# microcontroller.net
KiCad netlist of a schematic drawn in Altium Designer
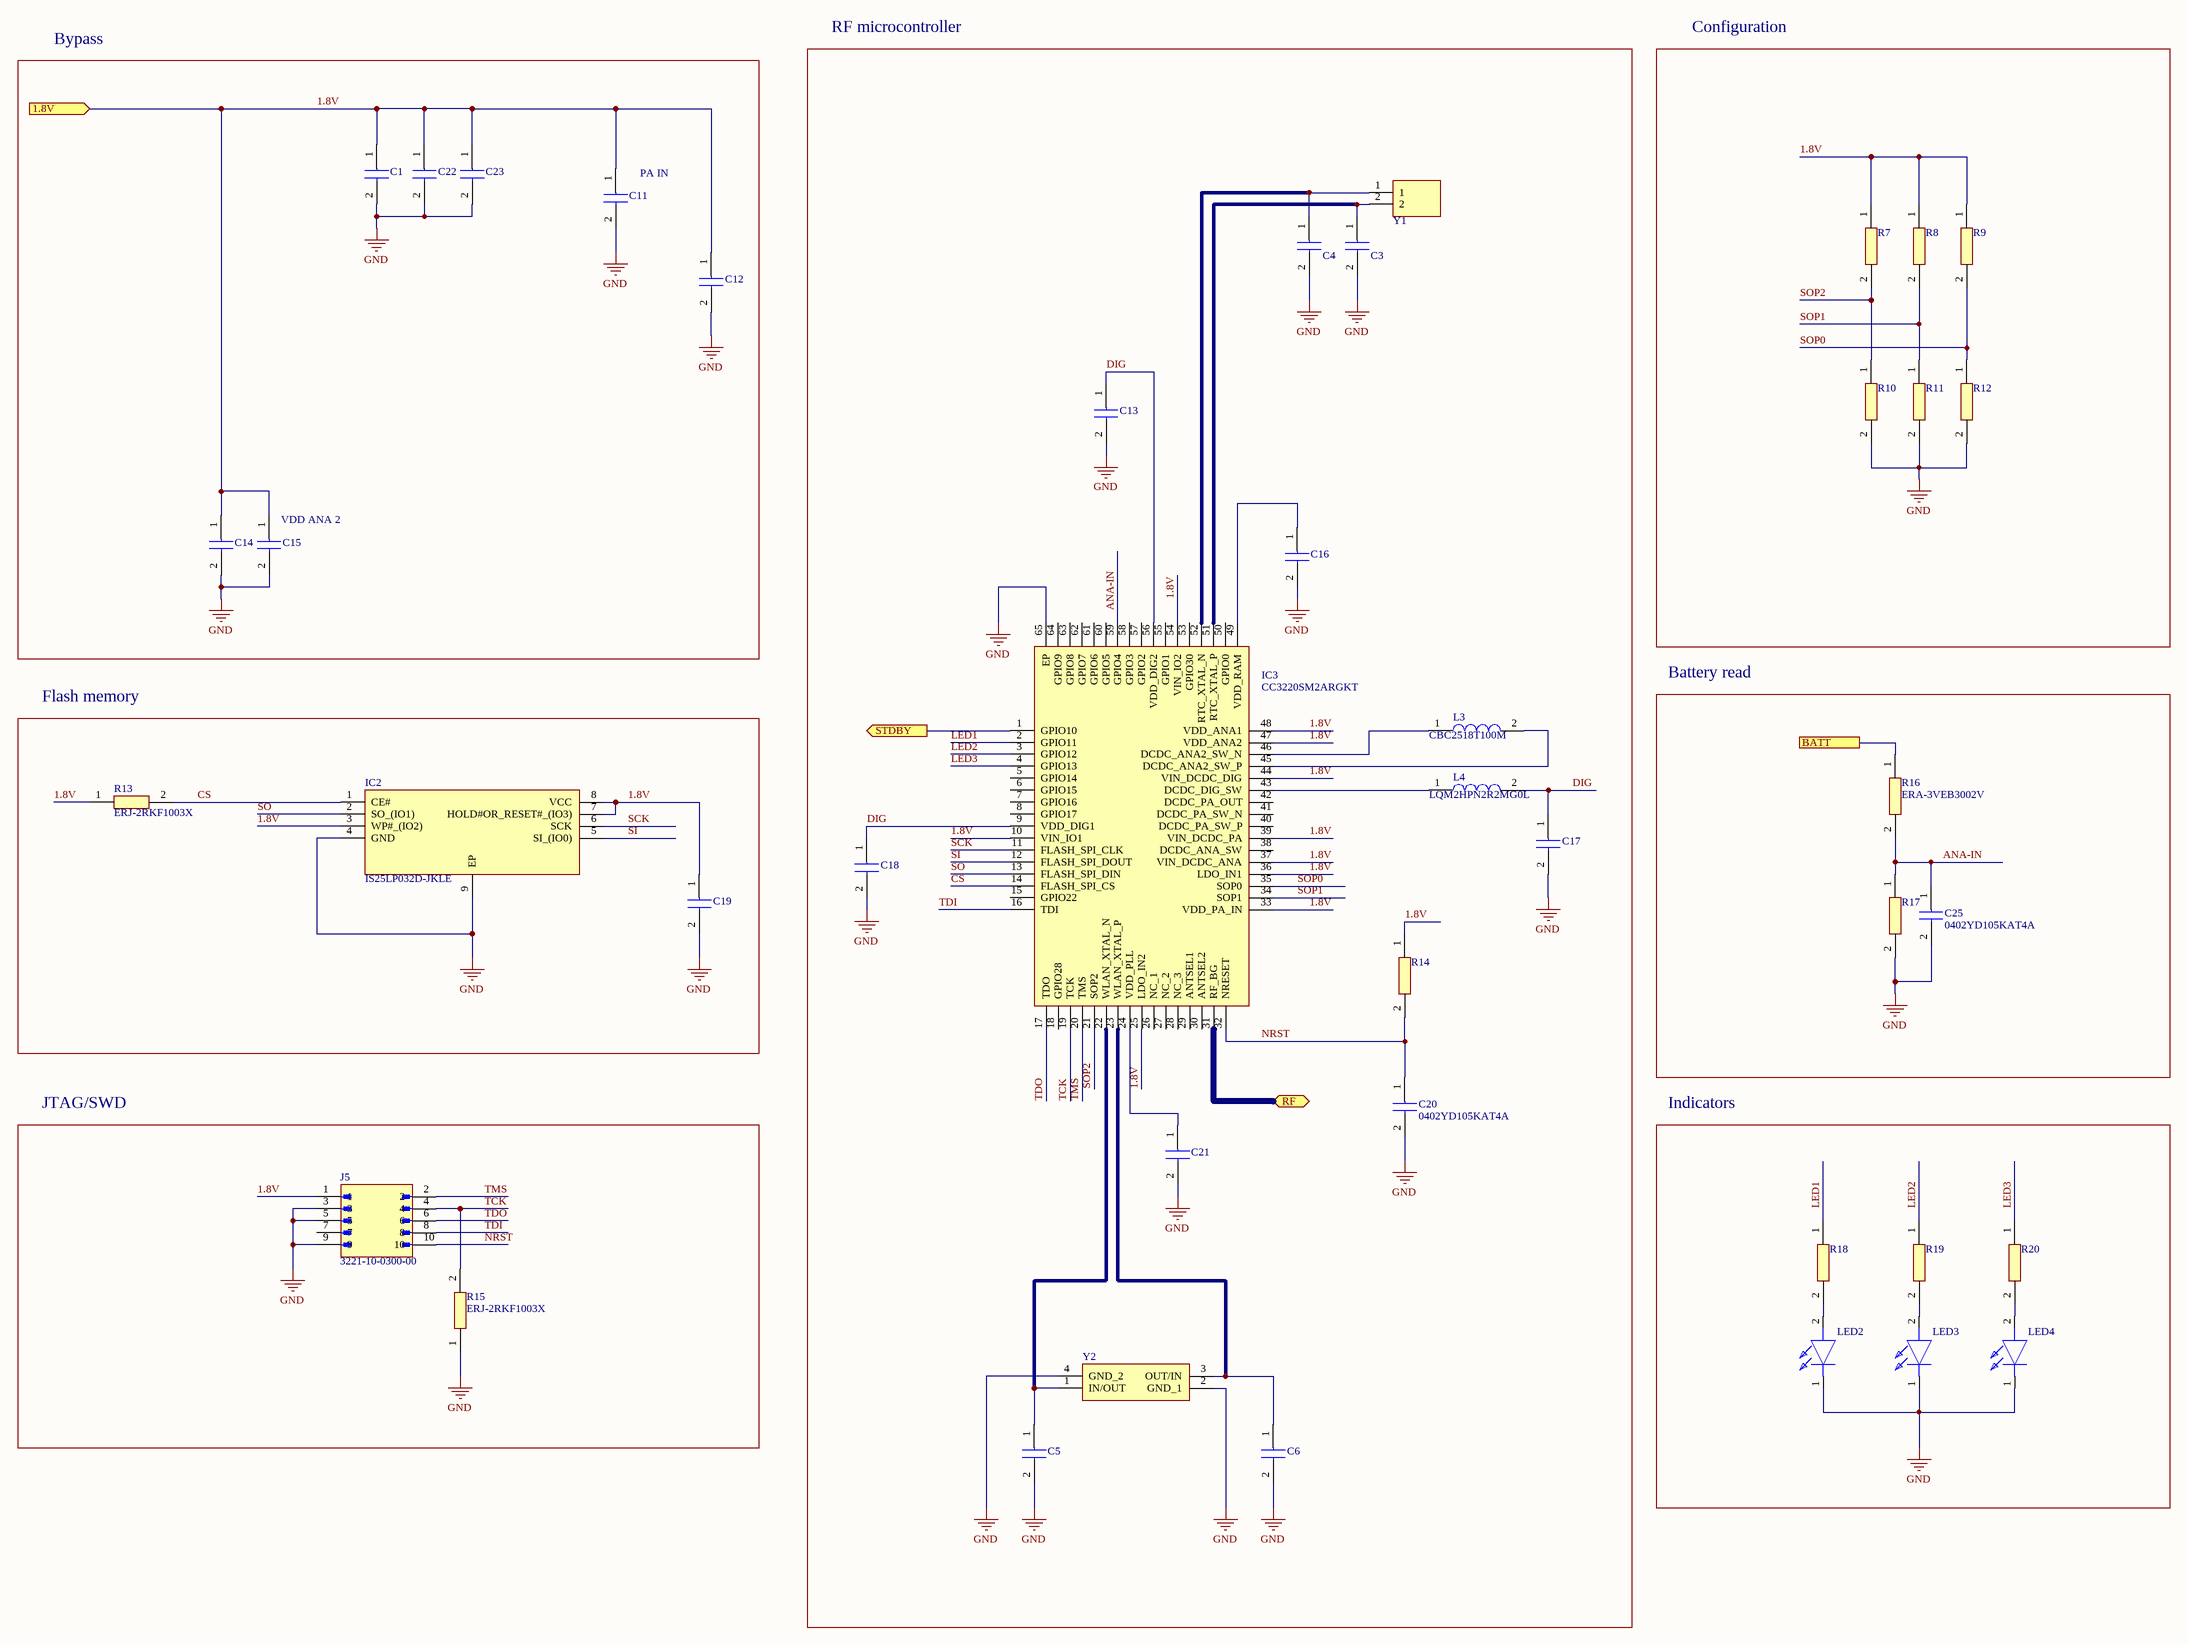
[diagram p0: microcontroller.SchDoc]

(export (version "E")
  (design (tool "Eeschema 10.0.6"))
  (components
    (comp (ref "C1")
      (value "C1005X5R0J475M050BC")
      (footprint "SamacSys:C1005_Commercial")
      (description "Capacitor")
      (fields (field (name "MOUSER PART NUMBER") "810-C1005X5R0J475M"))
      (libsource (lib "*") (part "C1005X5R0J475M050BC"))
    )
    (comp (ref "C3")
      (value "GRM1555C1H100JA01D")
      (footprint "SamacSys:CAPC1005X55N")
      (description "Capacitor")
      (fields (field (name "MOUSER PART NUMBER") "81-GRM1555C1H100JA1D"))
      (libsource (lib "*") (part "GRM1555C1H100JA01D"))
    )
    (comp (ref "C4")
      (value "GRM1555C1H100JA01D")
      (footprint "SamacSys:CAPC1005X55N")
      (description "Capacitor")
      (fields (field (name "MOUSER PART NUMBER") "81-GRM1555C1H100JA1D"))
      (libsource (lib "*") (part "GRM1555C1H100JA01D"))
    )
    (comp (ref "C5")
      (value "GRM1555C1H6R2CA01D")
      (footprint "SamacSys:CAPC1005X55N")
      (description "Capacitor")
      (fields (field (name "MOUSER PART NUMBER") "81-GRM1555C1H6R2CA1D"))
      (libsource (lib "*") (part "GRM1555C1H6R2CA01D"))
    )
    (comp (ref "C6")
      (value "GRM1555C1H6R2CA01D")
      (footprint "SamacSys:CAPC1005X55N")
      (description "Capacitor")
      (fields (field (name "MOUSER PART NUMBER") "81-GRM1555C1H6R2CA1D"))
      (libsource (lib "*") (part "GRM1555C1H6R2CA01D"))
    )
    (comp (ref "C11")
      (value "GRM158R60J226ME01D")
      (footprint "SamacSys:CAPC1005X80N")
      (description "Capacitor")
      (fields (field (name "MOUSER PART NUMBER") "81-GRM158R60J226ME1D"))
      (libsource (lib "*") (part "GRM158R60J226ME01D"))
    )
    (comp (ref "C12")
      (value "0402YD105KAT4A")
      (footprint "SamacSys:CAPC1005X56N")
      (description "Capacitor")
      (fields (field (name "MOUSER PART NUMBER") "581-0402YD105KAT4A"))
      (libsource (lib "*") (part "0402YD105KAT4A"))
    )
    (comp (ref "C13")
      (value "C1005X7R1C104K050BC")
      (footprint "SamacSys:C1005_Commercial")
      (description "Capacitor")
      (fields (field (name "MOUSER PART NUMBER") "810-C1005X7R1C104K"))
      (libsource (lib "*") (part "C1005X7R1C104K050BC"))
    )
    (comp (ref "C14")
      (value "GRM155C80G106ME44D")
      (footprint "SamacSys:CAPC1005X55N")
      (description "Capacitor")
      (fields (field (name "MOUSER PART NUMBER") "81-GRM155C80G106ME44"))
      (libsource (lib "*") (part "GRM155C80G106ME44D"))
    )
    (comp (ref "C15")
      (value "GRM155C80G106ME44D")
      (footprint "SamacSys:CAPC1005X55N")
      (description "Capacitor")
      (fields (field (name "MOUSER PART NUMBER") "81-GRM155C80G106ME44"))
      (libsource (lib "*") (part "GRM155C80G106ME44D"))
    )
    (comp (ref "C16")
      (value "C1005X7R1C104K050BC")
      (footprint "SamacSys:C1005_Commercial")
      (description "Capacitor")
      (fields (field (name "MOUSER PART NUMBER") "810-C1005X7R1C104K"))
      (libsource (lib "*") (part "C1005X7R1C104K050BC"))
    )
    (comp (ref "C17")
      (value "GRM155C80G106ME44D")
      (footprint "SamacSys:CAPC1005X55N")
      (description "Capacitor")
      (fields (field (name "MOUSER PART NUMBER") "81-GRM155C80G106ME44"))
      (libsource (lib "*") (part "GRM155C80G106ME44D"))
    )
    (comp (ref "C18")
      (value "C1005X7R1C104K050BC")
      (footprint "SamacSys:C1005_Commercial")
      (description "Capacitor")
      (fields (field (name "MOUSER PART NUMBER") "810-C1005X7R1C104K"))
      (libsource (lib "*") (part "C1005X7R1C104K050BC"))
    )
    (comp (ref "C19")
      (value "C1005X7R1C104K050BC")
      (footprint "SamacSys:C1005_Commercial")
      (description "Capacitor")
      (fields (field (name "MOUSER PART NUMBER") "810-C1005X7R1C104K"))
      (libsource (lib "*") (part "C1005X7R1C104K050BC"))
    )
    (comp (ref "C20")
      (value "0402YD105KAT4A")
      (footprint "SamacSys:CAPC1005X56N")
      (description "Capacitor")
      (fields (field (name "MOUSER PART NUMBER") "581-0402YD105KAT4A"))
      (libsource (lib "*") (part "0402YD105KAT4A"))
    )
    (comp (ref "C21")
      (value "C1005X7R1C104K050BC")
      (footprint "SamacSys:C1005_Commercial")
      (description "Capacitor")
      (fields (field (name "MOUSER PART NUMBER") "810-C1005X7R1C104K"))
      (libsource (lib "*") (part "C1005X7R1C104K050BC"))
    )
    (comp (ref "C22")
      (value "C1005X5R0J475M050BC")
      (footprint "SamacSys:C1005_Commercial")
      (description "Capacitor")
      (fields (field (name "MOUSER PART NUMBER") "810-C1005X5R0J475M"))
      (libsource (lib "*") (part "C1005X5R0J475M050BC"))
    )
    (comp (ref "C23")
      (value "C1005X5R0J475M050BC")
      (footprint "SamacSys:C1005_Commercial")
      (description "Capacitor")
      (fields (field (name "MOUSER PART NUMBER") "810-C1005X5R0J475M"))
      (libsource (lib "*") (part "C1005X5R0J475M050BC"))
    )
    (comp (ref "C25")
      (value "0402YD105KAT4A")
      (footprint "SamacSys:CAPC1005X56N")
      (description "Capacitor")
      (fields (field (name "MOUSER PART NUMBER") "581-0402YD105KAT4A"))
      (libsource (lib "*") (part "0402YD105KAT4A"))
    )
    (comp (ref "IC2")
      (value "IS25LP032D-JKLE")
      (footprint "SamacSys:SON127P600X500X80-9N-D")
      (description "Integrated Circuit")
      (fields (field (name "MOUSER PART NUMBER") "870-IS25LP032D-JKLE"))
      (libsource (lib "*") (part "IS25LP032D-JKLE"))
    )
    (comp (ref "IC3")
      (value "CC3220SM2ARGKT")
      (footprint "SamacSys:QFN50P900X900X100-65N-D")
      (description "Integrated Circuit")
      (fields (field (name "MOUSER PART NUMBER") "595-CC3220SM2ARGKT"))
      (libsource (lib "*") (part "CC3220SM2ARGKT"))
    )
    (comp (ref "J5")
      (value "3221-10-0300-00")
      (footprint "CNC_3221-10-0300-00")
      (description "Connector Header Surface Mount 10 position 0.050 (1.27mm)")
      (fields (field (name "MF") "CNC Tech"))
      (libsource (lib "3221-10-0300-00") (part "3221-10-0300-00"))
    )
    (comp (ref "L3")
      (value "CBC2518T100M")
      (footprint "SamacSys:INDC2518X180N")
      (description "Inductor")
      (fields (field (name "MOUSER PART NUMBER") "963-CBC2518T100M"))
      (libsource (lib "SamacSys") (part "CBC2518T100M"))
    )
    (comp (ref "L4")
      (value "LQM2HPN2R2MG0L")
      (footprint "SamacSys:INDC2520X100N")
      (description "Inductor")
      (fields (field (name "MOUSER PART NUMBER") "81-LQM2HPN2R2MG0L"))
      (libsource (lib "SamacSys") (part "LQM2HPN2R2MG0L"))
    )
    (comp (ref "LED2")
      (value "LT_QH9G-Q2OO-25-2Z4Y")
      (footprint "SamacSys:LEDC1005X40N")
      (description "LED")
      (fields
        (field (name "MANUFACTURER_PART_NUMBER") "LT QH9G-Q2OO-25-2Z4Y")
        (field (name "MOUSER PART NUMBER") "720-LTQH9GQ2S225")
      )
      (libsource (lib "*") (part "LT_QH9G-Q2OO-25-2Z4Y"))
    )
    (comp (ref "LED3")
      (value "LT_QH9G-Q2OO-25-2Z4Y")
      (footprint "SamacSys:LEDC1005X40N")
      (description "LED")
      (fields
        (field (name "MANUFACTURER_PART_NUMBER") "LT QH9G-Q2OO-25-2Z4Y")
        (field (name "MOUSER PART NUMBER") "720-LTQH9GQ2S225")
      )
      (libsource (lib "*") (part "LT_QH9G-Q2OO-25-2Z4Y"))
    )
    (comp (ref "LED4")
      (value "LT_QH9G-Q2OO-25-2Z4Y")
      (footprint "SamacSys:LEDC1005X40N")
      (description "LED")
      (fields
        (field (name "MANUFACTURER_PART_NUMBER") "LT QH9G-Q2OO-25-2Z4Y")
        (field (name "MOUSER PART NUMBER") "720-LTQH9GQ2S225")
      )
      (libsource (lib "*") (part "LT_QH9G-Q2OO-25-2Z4Y"))
    )
    (comp (ref "R7")
      (value "ERJ-2RKF1003X")
      (footprint "SamacSys:ERJ2R_(0402)")
      (description "Resistor")
      (fields (field (name "MOUSER PART NUMBER") "667-ERJ-2RKF1003X"))
      (libsource (lib "*") (part "ERJ-2RKF1003X"))
    )
    (comp (ref "R8")
      (value "ERJ-2RKF1003X")
      (footprint "SamacSys:ERJ2R_(0402)")
      (description "Resistor")
      (fields (field (name "MOUSER PART NUMBER") "667-ERJ-2RKF1003X"))
      (libsource (lib "*") (part "ERJ-2RKF1003X"))
    )
    (comp (ref "R9")
      (value "ERJ-2RKF1003X")
      (footprint "SamacSys:ERJ2R_(0402)")
      (description "Resistor")
      (fields (field (name "MOUSER PART NUMBER") "667-ERJ-2RKF1003X"))
      (libsource (lib "*") (part "ERJ-2RKF1003X"))
    )
    (comp (ref "R10")
      (value "ERJ-2RKF1003X")
      (footprint "SamacSys:ERJ2R_(0402)")
      (description "Resistor")
      (fields (field (name "MOUSER PART NUMBER") "667-ERJ-2RKF1003X"))
      (libsource (lib "*") (part "ERJ-2RKF1003X"))
    )
    (comp (ref "R11")
      (value "ERJ-2RKF1003X")
      (footprint "SamacSys:ERJ2R_(0402)")
      (description "Resistor")
      (fields (field (name "MOUSER PART NUMBER") "667-ERJ-2RKF1003X"))
      (libsource (lib "*") (part "ERJ-2RKF1003X"))
    )
    (comp (ref "R12")
      (value "ERJ-2RKF1003X")
      (footprint "SamacSys:ERJ2R_(0402)")
      (description "Resistor")
      (fields (field (name "MOUSER PART NUMBER") "667-ERJ-2RKF1003X"))
      (libsource (lib "*") (part "ERJ-2RKF1003X"))
    )
    (comp (ref "R13")
      (value "ERJ-2RKF1003X")
      (footprint "SamacSys:ERJ2R_(0402)")
      (description "Resistor")
      (fields (field (name "MOUSER PART NUMBER") "667-ERJ-2RKF1003X"))
      (libsource (lib "") (part "ERJ-2RKF1003X_2"))
    )
    (comp (ref "R14")
      (value "ERJ-2RKF1003X")
      (footprint "SamacSys:ERJ2R_(0402)")
      (description "Resistor")
      (fields (field (name "MOUSER PART NUMBER") "667-ERJ-2RKF1003X"))
      (libsource (lib "*") (part "ERJ-2RKF1003X"))
    )
    (comp (ref "R15")
      (value "ERJ-2RKF1003X")
      (footprint "SamacSys:ERJ2R_(0402)")
      (description "Resistor")
      (fields (field (name "MOUSER PART NUMBER") "667-ERJ-2RKF1003X"))
      (libsource (lib "") (part "ERJ-2RKF1003X_1"))
    )
    (comp (ref "R16")
      (value "ERA-3VEB3002V")
      (footprint "SamacSys:ERA3KV_(0603)")
      (description "Resistor")
      (fields (field (name "MOUSER PART NUMBER") "667-ERA-3VEB3002V"))
      (libsource (lib "*") (part "ERA-3VEB3002V"))
    )
    (comp (ref "R17")
      (value "RT0603BRD0750KL")
      (footprint "SamacSys:RESC1608X55N")
      (description "Resistor")
      (fields (field (name "MOUSER PART NUMBER") "603-RT0603BRD0750KL"))
      (libsource (lib "*") (part "RT0603BRD0750KL"))
    )
    (comp (ref "R18")
      (value "CR0402-FX-6200GLF")
      (footprint "SamacSys:RESC1005X40N")
      (description "Resistor")
      (fields (field (name "MOUSER PART NUMBER") "652-CR0402FX-6200GLF"))
      (libsource (lib "*") (part "CR0402-FX-6200GLF"))
    )
    (comp (ref "R19")
      (value "CR0402-FX-6200GLF")
      (footprint "SamacSys:RESC1005X40N")
      (description "Resistor")
      (fields (field (name "MOUSER PART NUMBER") "652-CR0402FX-6200GLF"))
      (libsource (lib "*") (part "CR0402-FX-6200GLF"))
    )
    (comp (ref "R20")
      (value "CR0402-FX-6200GLF")
      (footprint "SamacSys:RESC1005X40N")
      (description "Resistor")
      (fields (field (name "MOUSER PART NUMBER") "652-CR0402FX-6200GLF"))
      (libsource (lib "*") (part "CR0402-FX-6200GLF"))
    )
    (comp (ref "Y1")
      (value "ABS07-32.768KHZ-9-T")
      (footprint "SamacSys:ABS-07")
      (description "Integrated Circuit")
      (fields (field (name "MOUSER PART NUMBER") "815-ABS07-32.768K9T"))
      (libsource (lib "*") (part "ABS07-32.768KHZ-9-T"))
    )
    (comp (ref "Y2")
      (value "ECS-400-8-36B-7KY-TR")
      (footprint "SamacSys:ECS400836B7KYTR")
      (description "Crystal or Oscillator")
      (libsource (lib "SamacSys") (part "ECS-400-8-36B-7KY-TR"))
    )
  )
  (nets
    (net (code "1") (name "/1.8V") (class "Default")
      (node (ref "C1") (pin "1") (pinfunction "1_1") (pintype "passive"))
      (node (ref "C11") (pin "1") (pinfunction "1_1") (pintype "passive"))
      (node (ref "C12") (pin "1") (pinfunction "1_1") (pintype "passive"))
      (node (ref "C14") (pin "1") (pinfunction "1_1") (pintype "passive"))
      (node (ref "C15") (pin "1") (pinfunction "1_1") (pintype "passive"))
      (node (ref "C19") (pin "1") (pinfunction "1_1") (pintype "passive"))
      (node (ref "C22") (pin "1") (pinfunction "1_1") (pintype "passive"))
      (node (ref "C23") (pin "1") (pinfunction "1_1") (pintype "passive"))
      (node (ref "IC2") (pin "3") (pinfunction "WP#_(IO2)_3") (pintype "passive"))
      (node (ref "IC2") (pin "7") (pinfunction "HOLD#OR_RESET#_(IO3)_7") (pintype "passive"))
      (node (ref "IC2") (pin "8") (pinfunction "VCC_8") (pintype "passive"))
      (node (ref "IC3") (pin "10") (pinfunction "VIN_IO1_10") (pintype "passive"))
      (node (ref "IC3") (pin "25") (pinfunction "LDO_IN2_25") (pintype "passive"))
      (node (ref "IC3") (pin "33") (pinfunction "VDD_PA_IN_33") (pintype "passive"))
      (node (ref "IC3") (pin "36") (pinfunction "LDO_IN1_36") (pintype "passive"))
      (node (ref "IC3") (pin "37") (pinfunction "VIN_DCDC_ANA_37") (pintype "passive"))
      (node (ref "IC3") (pin "39") (pinfunction "VIN_DCDC_PA_39") (pintype "passive"))
      (node (ref "IC3") (pin "44") (pinfunction "VIN_DCDC_DIG_44") (pintype "passive"))
      (node (ref "IC3") (pin "47") (pinfunction "VDD_ANA2_47") (pintype "passive"))
      (node (ref "IC3") (pin "48") (pinfunction "VDD_ANA1_48") (pintype "passive"))
      (node (ref "IC3") (pin "54") (pinfunction "VIN_IO2_54") (pintype "passive"))
      (node (ref "J5") (pin "1") (pinfunction "1_1") (pintype "passive"))
      (node (ref "R13") (pin "1") (pinfunction "1_1") (pintype "passive"))
      (node (ref "R14") (pin "1") (pinfunction "1_1") (pintype "passive"))
      (node (ref "R7") (pin "1") (pinfunction "1_1") (pintype "passive"))
      (node (ref "R8") (pin "1") (pinfunction "1_1") (pintype "passive"))
      (node (ref "R9") (pin "1") (pinfunction "1_1") (pintype "passive"))
    )
    (net (code "2") (name "/ANA-IN") (class "Default")
      (node (ref "C25") (pin "1") (pinfunction "1_1") (pintype "passive"))
      (node (ref "IC3") (pin "59") (pinfunction "GPIO4_59") (pintype "passive"))
      (node (ref "R16") (pin "2") (pinfunction "2_2") (pintype "passive"))
      (node (ref "R17") (pin "1") (pinfunction "1_1") (pintype "passive"))
    )
    (net (code "3") (name "/BATT") (class "Default")
      (node (ref "R16") (pin "1") (pinfunction "1_1") (pintype "passive"))
    )
    (net (code "4") (name "/CS") (class "Default")
      (node (ref "IC2") (pin "1") (pinfunction "CE#_1") (pintype "passive"))
      (node (ref "IC3") (pin "14") (pinfunction "FLASH_SPI_CS_14") (pintype "passive"))
      (node (ref "R13") (pin "2") (pinfunction "2_2") (pintype "passive"))
    )
    (net (code "5") (name "/DIG") (class "Default")
      (node (ref "C13") (pin "1") (pinfunction "1_1") (pintype "passive"))
      (node (ref "C17") (pin "1") (pinfunction "1_1") (pintype "passive"))
      (node (ref "C18") (pin "1") (pinfunction "1_1") (pintype "passive"))
      (node (ref "IC3") (pin "56") (pinfunction "VDD_DIG2_56") (pintype "passive"))
      (node (ref "IC3") (pin "9") (pinfunction "VDD_DIG1_9") (pintype "passive"))
      (node (ref "L4") (pin "2") (pinfunction "2_2") (pintype "passive"))
    )
    (net (code "6") (name "/LED1") (class "Default")
      (node (ref "IC3") (pin "2") (pinfunction "GPIO11_2") (pintype "passive"))
      (node (ref "R18") (pin "1") (pinfunction "1_1") (pintype "passive"))
    )
    (net (code "7") (name "/LED2") (class "Default")
      (node (ref "IC3") (pin "3") (pinfunction "GPIO12_3") (pintype "passive"))
      (node (ref "R19") (pin "1") (pinfunction "1_1") (pintype "passive"))
    )
    (net (code "8") (name "/LED3") (class "Default")
      (node (ref "IC3") (pin "4") (pinfunction "GPIO13_4") (pintype "passive"))
      (node (ref "R20") (pin "1") (pinfunction "1_1") (pintype "passive"))
    )
    (net (code "9") (name "/NRST") (class "Default")
      (node (ref "C20") (pin "1") (pinfunction "1_1") (pintype "passive"))
      (node (ref "IC3") (pin "32") (pinfunction "NRESET_32") (pintype "passive"))
      (node (ref "J5") (pin "10") (pinfunction "10_10") (pintype "passive"))
      (node (ref "R14") (pin "2") (pinfunction "2_2") (pintype "passive"))
    )
    (net (code "10") (name "/RF") (class "Default")
      (node (ref "IC3") (pin "31") (pinfunction "RF_BG_31") (pintype "passive"))
    )
    (net (code "11") (name "/SCK") (class "Default")
      (node (ref "IC2") (pin "6") (pinfunction "SCK_6") (pintype "passive"))
      (node (ref "IC3") (pin "11") (pinfunction "FLASH_SPI_CLK_11") (pintype "passive"))
    )
    (net (code "12") (name "/SI") (class "Default")
      (node (ref "IC2") (pin "5") (pinfunction "SI_(IO0)_5") (pintype "passive"))
      (node (ref "IC3") (pin "12") (pinfunction "FLASH_SPI_DOUT_12") (pintype "passive"))
    )
    (net (code "13") (name "/SO") (class "Default")
      (node (ref "IC2") (pin "2") (pinfunction "SO_(IO1)_2") (pintype "passive"))
      (node (ref "IC3") (pin "13") (pinfunction "FLASH_SPI_DIN_13") (pintype "passive"))
    )
    (net (code "14") (name "/SOP0") (class "Default")
      (node (ref "IC3") (pin "35") (pinfunction "SOP0_35") (pintype "passive"))
      (node (ref "R12") (pin "1") (pinfunction "1_1") (pintype "passive"))
      (node (ref "R9") (pin "2") (pinfunction "2_2") (pintype "passive"))
    )
    (net (code "15") (name "/SOP1") (class "Default")
      (node (ref "IC3") (pin "34") (pinfunction "SOP1_34") (pintype "passive"))
      (node (ref "R11") (pin "1") (pinfunction "1_1") (pintype "passive"))
      (node (ref "R8") (pin "2") (pinfunction "2_2") (pintype "passive"))
    )
    (net (code "16") (name "/SOP2") (class "Default")
      (node (ref "IC3") (pin "21") (pinfunction "SOP2_21") (pintype "passive"))
      (node (ref "R10") (pin "1") (pinfunction "1_1") (pintype "passive"))
      (node (ref "R7") (pin "2") (pinfunction "2_2") (pintype "passive"))
    )
    (net (code "17") (name "/STDBY") (class "Default")
      (node (ref "IC3") (pin "1") (pinfunction "GPIO10_1") (pintype "passive"))
    )
    (net (code "18") (name "/TCK") (class "Default")
      (node (ref "IC3") (pin "19") (pinfunction "TCK_19") (pintype "passive"))
      (node (ref "J5") (pin "4") (pinfunction "4_4") (pintype "passive"))
      (node (ref "R15") (pin "2") (pinfunction "2_2") (pintype "passive"))
    )
    (net (code "19") (name "/TDI") (class "Default")
      (node (ref "IC3") (pin "16") (pinfunction "TDI_16") (pintype "passive"))
      (node (ref "J5") (pin "8") (pinfunction "8_8") (pintype "passive"))
    )
    (net (code "20") (name "/TDO") (class "Default")
      (node (ref "IC3") (pin "17") (pinfunction "TDO_17") (pintype "passive"))
      (node (ref "J5") (pin "6") (pinfunction "6_6") (pintype "passive"))
    )
    (net (code "21") (name "/TMS") (class "Default")
      (node (ref "IC3") (pin "20") (pinfunction "TMS_20") (pintype "passive"))
      (node (ref "J5") (pin "2") (pinfunction "2_2") (pintype "passive"))
    )
    (net (code "22") (name "GND") (class "Default")
      (node (ref "C1") (pin "2") (pinfunction "2_2") (pintype "passive"))
      (node (ref "C11") (pin "2") (pinfunction "2_2") (pintype "passive"))
      (node (ref "C12") (pin "2") (pinfunction "2_2") (pintype "passive"))
      (node (ref "C13") (pin "2") (pinfunction "2_2") (pintype "passive"))
      (node (ref "C14") (pin "2") (pinfunction "2_2") (pintype "passive"))
      (node (ref "C15") (pin "2") (pinfunction "2_2") (pintype "passive"))
      (node (ref "C16") (pin "2") (pinfunction "2_2") (pintype "passive"))
      (node (ref "C17") (pin "2") (pinfunction "2_2") (pintype "passive"))
      (node (ref "C18") (pin "2") (pinfunction "2_2") (pintype "passive"))
      (node (ref "C19") (pin "2") (pinfunction "2_2") (pintype "passive"))
      (node (ref "C20") (pin "2") (pinfunction "2_2") (pintype "passive"))
      (node (ref "C21") (pin "2") (pinfunction "2_2") (pintype "passive"))
      (node (ref "C22") (pin "2") (pinfunction "2_2") (pintype "passive"))
      (node (ref "C23") (pin "2") (pinfunction "2_2") (pintype "passive"))
      (node (ref "C25") (pin "2") (pinfunction "2_2") (pintype "passive"))
      (node (ref "C3") (pin "2") (pinfunction "2_2") (pintype "passive"))
      (node (ref "C4") (pin "2") (pinfunction "2_2") (pintype "passive"))
      (node (ref "C5") (pin "2") (pinfunction "2_2") (pintype "passive"))
      (node (ref "C6") (pin "2") (pinfunction "2_2") (pintype "passive"))
      (node (ref "IC2") (pin "4") (pinfunction "GND_4") (pintype "passive"))
      (node (ref "IC2") (pin "9") (pinfunction "EP_9") (pintype "passive"))
      (node (ref "IC3") (pin "65") (pinfunction "EP_65") (pintype "passive"))
      (node (ref "J5") (pin "3") (pinfunction "3_3") (pintype "passive"))
      (node (ref "J5") (pin "5") (pinfunction "5_5") (pintype "passive"))
      (node (ref "J5") (pin "9") (pinfunction "9_9") (pintype "passive"))
      (node (ref "LED2") (pin "1") (pinfunction "K_1") (pintype "passive"))
      (node (ref "LED3") (pin "1") (pinfunction "K_1") (pintype "passive"))
      (node (ref "LED4") (pin "1") (pinfunction "K_1") (pintype "passive"))
      (node (ref "R10") (pin "2") (pinfunction "2_2") (pintype "passive"))
      (node (ref "R11") (pin "2") (pinfunction "2_2") (pintype "passive"))
      (node (ref "R12") (pin "2") (pinfunction "2_2") (pintype "passive"))
      (node (ref "R15") (pin "1") (pinfunction "1_1") (pintype "passive"))
      (node (ref "R17") (pin "2") (pinfunction "2_2") (pintype "passive"))
      (node (ref "Y2") (pin "2") (pinfunction "GND_1_2") (pintype "passive"))
      (node (ref "Y2") (pin "4") (pinfunction "GND_2_4") (pintype "passive"))
    )
    (net (code "23") (name "Net-(IC3-DCDC_ANA2_SW_N)") (class "Default")
      (node (ref "IC3") (pin "46") (pinfunction "DCDC_ANA2_SW_N_46") (pintype "passive"))
      (node (ref "L3") (pin "1") (pinfunction "1_1") (pintype "passive"))
    )
    (net (code "24") (name "Net-(IC3-DCDC_ANA2_SW_P)") (class "Default")
      (node (ref "IC3") (pin "45") (pinfunction "DCDC_ANA2_SW_P_45") (pintype "passive"))
      (node (ref "L3") (pin "2") (pinfunction "2_2") (pintype "passive"))
    )
    (net (code "25") (name "Net-(IC3-DCDC_DIG_SW)") (class "Default")
      (node (ref "IC3") (pin "43") (pinfunction "DCDC_DIG_SW_43") (pintype "passive"))
      (node (ref "L4") (pin "1") (pinfunction "1_1") (pintype "passive"))
    )
    (net (code "26") (name "Net-(IC3-RTC_XTAL_N)") (class "Default")
      (node (ref "C4") (pin "1") (pinfunction "1_1") (pintype "passive"))
      (node (ref "IC3") (pin "52") (pinfunction "RTC_XTAL_N_52") (pintype "passive"))
      (node (ref "Y1") (pin "1") (pinfunction "1_1") (pintype "passive"))
    )
    (net (code "27") (name "Net-(IC3-RTC_XTAL_P)") (class "Default")
      (node (ref "C3") (pin "1") (pinfunction "1_1") (pintype "passive"))
      (node (ref "IC3") (pin "51") (pinfunction "RTC_XTAL_P_51") (pintype "passive"))
      (node (ref "Y1") (pin "2") (pinfunction "2_2") (pintype "passive"))
    )
    (net (code "28") (name "Net-(IC3-VDD_PLL)") (class "Default")
      (node (ref "C21") (pin "1") (pinfunction "1_1") (pintype "passive"))
      (node (ref "IC3") (pin "24") (pinfunction "VDD_PLL_24") (pintype "passive"))
    )
    (net (code "29") (name "Net-(IC3-VDD_RAM)") (class "Default")
      (node (ref "C16") (pin "1") (pinfunction "1_1") (pintype "passive"))
      (node (ref "IC3") (pin "49") (pinfunction "VDD_RAM_49") (pintype "passive"))
    )
    (net (code "30") (name "Net-(IC3-WLAN_XTAL_N)") (class "Default")
      (node (ref "C5") (pin "1") (pinfunction "1_1") (pintype "passive"))
      (node (ref "IC3") (pin "22") (pinfunction "WLAN_XTAL_N_22") (pintype "passive"))
      (node (ref "Y2") (pin "1") (pinfunction "IN/OUT_1") (pintype "passive"))
    )
    (net (code "31") (name "Net-(IC3-WLAN_XTAL_P)") (class "Default")
      (node (ref "C6") (pin "1") (pinfunction "1_1") (pintype "passive"))
      (node (ref "IC3") (pin "23") (pinfunction "WLAN_XTAL_P_23") (pintype "passive"))
      (node (ref "Y2") (pin "3") (pinfunction "OUT/IN_3") (pintype "passive"))
    )
    (net (code "32") (name "Net-(LED2-A)") (class "Default")
      (node (ref "LED2") (pin "2") (pinfunction "A_2") (pintype "passive"))
      (node (ref "R18") (pin "2") (pinfunction "2_2") (pintype "passive"))
    )
    (net (code "33") (name "Net-(LED3-A)") (class "Default")
      (node (ref "LED3") (pin "2") (pinfunction "A_2") (pintype "passive"))
      (node (ref "R19") (pin "2") (pinfunction "2_2") (pintype "passive"))
    )
    (net (code "34") (name "Net-(LED4-A)") (class "Default")
      (node (ref "LED4") (pin "2") (pinfunction "A_2") (pintype "passive"))
      (node (ref "R20") (pin "2") (pinfunction "2_2") (pintype "passive"))
    )
    (net (code "35") (name "unconnected-(IC3-ANTSEL1-Pad29)") (class "Default")
      (node (ref "IC3") (pin "29") (pinfunction "ANTSEL1_29") (pintype "passive"))
    )
    (net (code "36") (name "unconnected-(IC3-ANTSEL2-Pad30)") (class "Default")
      (node (ref "IC3") (pin "30") (pinfunction "ANTSEL2_30") (pintype "passive"))
    )
    (net (code "37") (name "unconnected-(IC3-DCDC_ANA_SW-Pad38)") (class "Default")
      (node (ref "IC3") (pin "38") (pinfunction "DCDC_ANA_SW_38") (pintype "passive"))
    )
    (net (code "38") (name "unconnected-(IC3-DCDC_PA_OUT-Pad42)") (class "Default")
      (node (ref "IC3") (pin "42") (pinfunction "DCDC_PA_OUT_42") (pintype "passive"))
    )
    (net (code "39") (name "unconnected-(IC3-DCDC_PA_SW_N-Pad41)") (class "Default")
      (node (ref "IC3") (pin "41") (pinfunction "DCDC_PA_SW_N_41") (pintype "passive"))
    )
    (net (code "40") (name "unconnected-(IC3-DCDC_PA_SW_P-Pad40)") (class "Default")
      (node (ref "IC3") (pin "40") (pinfunction "DCDC_PA_SW_P_40") (pintype "passive"))
    )
    (net (code "41") (name "unconnected-(IC3-GPIO0-Pad50)") (class "Default")
      (node (ref "IC3") (pin "50") (pinfunction "GPIO0_50") (pintype "passive"))
    )
    (net (code "42") (name "unconnected-(IC3-GPIO1-Pad55)") (class "Default")
      (node (ref "IC3") (pin "55") (pinfunction "GPIO1_55") (pintype "passive"))
    )
    (net (code "43") (name "unconnected-(IC3-GPIO2-Pad57)") (class "Default")
      (node (ref "IC3") (pin "57") (pinfunction "GPIO2_57") (pintype "passive"))
    )
    (net (code "44") (name "unconnected-(IC3-GPIO3-Pad58)") (class "Default")
      (node (ref "IC3") (pin "58") (pinfunction "GPIO3_58") (pintype "passive"))
    )
    (net (code "45") (name "unconnected-(IC3-GPIO5-Pad60)") (class "Default")
      (node (ref "IC3") (pin "60") (pinfunction "GPIO5_60") (pintype "passive"))
    )
    (net (code "46") (name "unconnected-(IC3-GPIO6-Pad61)") (class "Default")
      (node (ref "IC3") (pin "61") (pinfunction "GPIO6_61") (pintype "passive"))
    )
    (net (code "47") (name "unconnected-(IC3-GPIO7-Pad62)") (class "Default")
      (node (ref "IC3") (pin "62") (pinfunction "GPIO7_62") (pintype "passive"))
    )
    (net (code "48") (name "unconnected-(IC3-GPIO8-Pad63)") (class "Default")
      (node (ref "IC3") (pin "63") (pinfunction "GPIO8_63") (pintype "passive"))
    )
    (net (code "49") (name "unconnected-(IC3-GPIO9-Pad64)") (class "Default")
      (node (ref "IC3") (pin "64") (pinfunction "GPIO9_64") (pintype "passive"))
    )
    (net (code "50") (name "unconnected-(IC3-GPIO14-Pad5)") (class "Default")
      (node (ref "IC3") (pin "5") (pinfunction "GPIO14_5") (pintype "passive"))
    )
    (net (code "51") (name "unconnected-(IC3-GPIO15-Pad6)") (class "Default")
      (node (ref "IC3") (pin "6") (pinfunction "GPIO15_6") (pintype "passive"))
    )
    (net (code "52") (name "unconnected-(IC3-GPIO16-Pad7)") (class "Default")
      (node (ref "IC3") (pin "7") (pinfunction "GPIO16_7") (pintype "passive"))
    )
    (net (code "53") (name "unconnected-(IC3-GPIO17-Pad8)") (class "Default")
      (node (ref "IC3") (pin "8") (pinfunction "GPIO17_8") (pintype "passive"))
    )
    (net (code "54") (name "unconnected-(IC3-GPIO22-Pad15)") (class "Default")
      (node (ref "IC3") (pin "15") (pinfunction "GPIO22_15") (pintype "passive"))
    )
    (net (code "55") (name "unconnected-(IC3-GPIO28-Pad18)") (class "Default")
      (node (ref "IC3") (pin "18") (pinfunction "GPIO28_18") (pintype "passive"))
    )
    (net (code "56") (name "unconnected-(IC3-GPIO30-Pad53)") (class "Default")
      (node (ref "IC3") (pin "53") (pinfunction "GPIO30_53") (pintype "passive"))
    )
    (net (code "57") (name "unconnected-(IC3-NC_1-Pad26)") (class "Default")
      (node (ref "IC3") (pin "26") (pinfunction "NC_1_26") (pintype "passive"))
    )
    (net (code "58") (name "unconnected-(IC3-NC_2-Pad27)") (class "Default")
      (node (ref "IC3") (pin "27") (pinfunction "NC_2_27") (pintype "passive"))
    )
    (net (code "59") (name "unconnected-(IC3-NC_3-Pad28)") (class "Default")
      (node (ref "IC3") (pin "28") (pinfunction "NC_3_28") (pintype "passive"))
    )
    (net (code "60") (name "unconnected-(J5-Pad7)") (class "Default")
      (node (ref "J5") (pin "7") (pinfunction "7_7") (pintype "passive"))
    )
  )
)
